# design.net
KiCad netlist of a schematic drawn in Altium Designer
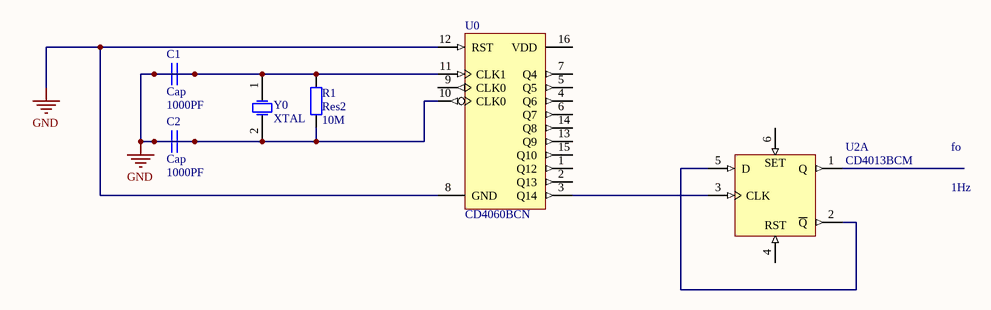
[diagram p0: 秒信号发生器.SchDoc]

(export (version "E")
  (design (tool "Eeschema 10.0.6"))
  (components
    (comp (ref "C1")
      (value "Cap")
      (footprint "RAD-0.3")
      (description "Capacitor")
      (fields (field (name "ALTIUM_VALUE") "1000PF") (field (name "PUBLISHER") "Altium Limited"))
      (libsource (lib "Miscellaneous Devices") (part "Cap"))
    )
    (comp (ref "C2")
      (value "Cap")
      (footprint "RAD-0.3")
      (description "Capacitor")
      (fields (field (name "ALTIUM_VALUE") "1000PF") (field (name "PUBLISHER") "Altium Limited"))
      (libsource (lib "Miscellaneous Devices") (part "Cap"))
    )
    (comp (ref "R1")
      (value "Res2")
      (footprint "AXIAL-0.4")
      (description "Resistor")
      (fields (field (name "ALTIUM_VALUE") "10M") (field (name "PUBLISHER") "Altium Limited"))
      (libsource (lib "Miscellaneous Devices") (part "Res2"))
    )
    (comp (ref "U0")
      (value "CD4060BCN")
      (footprint "N16E")
      (description "14-Stage Ripple Carry Binary Counter")
      (fields (field (name "PUBLISHER") "Altium Limited"))
      (libsource (lib "NSC Logic Counter") (part "CD4060BCN"))
    )
    (comp (ref "U2")
      (value "CD4013BCM")
      (footprint "M14A_N")
      (description "Dual D-Type Flip-Flop")
      (fields (field (name "PUBLISHER") "Altium Limited"))
      (libsource (lib "FSC Logic Flip-Flop") (part "CD4013BCM"))
    )
    (comp (ref "Y0")
      (value "XTAL")
      (footprint "R38")
      (description "Crystal Oscillator")
      (fields (field (name "PUBLISHER") "Altium Limited"))
      (libsource (lib "Miscellaneous Devices") (part "XTAL"))
    )
  )
  (nets
    (net (code "1") (name "GND") (class "Default")
      (node (ref "C1") (pin "1") (pinfunction "1_1") (pintype "passive"))
      (node (ref "C1") (pin "2") (pinfunction "2_2") (pintype "passive"))
      (node (ref "C2") (pin "1") (pinfunction "1_1") (pintype "passive"))
      (node (ref "C2") (pin "2") (pinfunction "2_2") (pintype "passive"))
      (node (ref "R1") (pin "1") (pinfunction "1_1") (pintype "passive"))
      (node (ref "R1") (pin "2") (pinfunction "2_2") (pintype "passive"))
      (node (ref "U0") (pin "10") (pinfunction "CLK0_10") (pintype "output"))
      (node (ref "U0") (pin "11") (pinfunction "CLK1_11") (pintype "input"))
      (node (ref "U0") (pin "12") (pinfunction "RST_12") (pintype "input"))
      (node (ref "U0") (pin "8") (pinfunction "GND_8") (pintype "power_in"))
      (node (ref "U2") (pin "7") (pinfunction "GND_7") (pintype "power_in"))
      (node (ref "Y0") (pin "1") (pinfunction "OSC1_1") (pintype "passive"))
      (node (ref "Y0") (pin "2") (pinfunction "OSC2_2") (pintype "passive"))
    )
    (net (code "2") (name "Net-(U0-Q14)") (class "Default")
      (node (ref "U0") (pin "3") (pinfunction "Q14_3") (pintype "output"))
      (node (ref "U2") (pin "3") (pinfunction "CLK_3") (pintype "input"))
    )
    (net (code "3") (name "Net-(U2A-D)") (class "Default")
      (node (ref "U2") (pin "2") (pinfunction "~{Q}_2") (pintype "output"))
      (node (ref "U2") (pin "5") (pinfunction "D_5") (pintype "input"))
    )
    (net (code "4") (name "VDD") (class "Default")
      (node (ref "U2") (pin "14") (pinfunction "VDD_14") (pintype "power_in"))
    )
    (net (code "5") (name "unconnected-(U0-CLK0-Pad9)") (class "Default")
      (node (ref "U0") (pin "9") (pinfunction "CLK0_9") (pintype "output"))
    )
    (net (code "6") (name "unconnected-(U0-Q4-Pad7)") (class "Default")
      (node (ref "U0") (pin "7") (pinfunction "Q4_7") (pintype "output"))
    )
    (net (code "7") (name "unconnected-(U0-Q5-Pad5)") (class "Default")
      (node (ref "U0") (pin "5") (pinfunction "Q5_5") (pintype "output"))
    )
    (net (code "8") (name "unconnected-(U0-Q6-Pad4)") (class "Default")
      (node (ref "U0") (pin "4") (pinfunction "Q6_4") (pintype "output"))
    )
    (net (code "9") (name "unconnected-(U0-Q7-Pad6)") (class "Default")
      (node (ref "U0") (pin "6") (pinfunction "Q7_6") (pintype "output"))
    )
    (net (code "10") (name "unconnected-(U0-Q8-Pad14)") (class "Default")
      (node (ref "U0") (pin "14") (pinfunction "Q8_14") (pintype "output"))
    )
    (net (code "11") (name "unconnected-(U0-Q9-Pad13)") (class "Default")
      (node (ref "U0") (pin "13") (pinfunction "Q9_13") (pintype "output"))
    )
    (net (code "12") (name "unconnected-(U0-Q10-Pad15)") (class "Default")
      (node (ref "U0") (pin "15") (pinfunction "Q10_15") (pintype "output"))
    )
    (net (code "13") (name "unconnected-(U0-Q12-Pad1)") (class "Default")
      (node (ref "U0") (pin "1") (pinfunction "Q12_1") (pintype "output"))
    )
    (net (code "14") (name "unconnected-(U0-Q13-Pad2)") (class "Default")
      (node (ref "U0") (pin "2") (pinfunction "Q13_2") (pintype "output"))
    )
    (net (code "15") (name "unconnected-(U0-VDD-Pad16)") (class "Default")
      (node (ref "U0") (pin "16") (pinfunction "VDD_16") (pintype "power_in"))
    )
    (net (code "16") (name "unconnected-(U2A-Q-Pad1)") (class "Default")
      (node (ref "U2") (pin "1") (pinfunction "Q_1") (pintype "output"))
    )
    (net (code "17") (name "unconnected-(U2A-RST-Pad4)") (class "Default")
      (node (ref "U2") (pin "4") (pinfunction "RST_4") (pintype "input"))
    )
    (net (code "18") (name "unconnected-(U2A-S-Pad6)") (class "Default")
      (node (ref "U2") (pin "6") (pinfunction "S_6") (pintype "input"))
    )
  )
)
